# 08_Secure_Element.net
KiCad netlist of a schematic drawn in Altium Designer
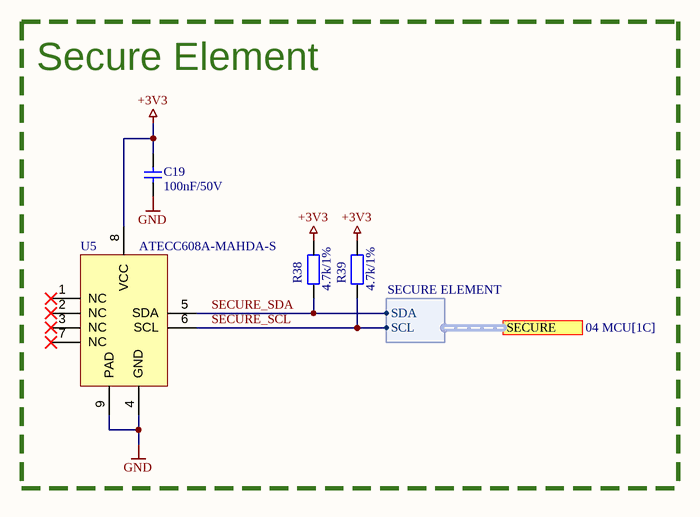
[diagram p0: 08 Secure Element.SchDoc]

(export (version "E")
  (design (tool "Eeschema 10.0.6"))
  (components
    (comp (ref "C19")
      (value "100nF/50V")
      (footprint "CAPC1005X06M-0402")
      (description "0.1 µF ±10% 50V Ceramic Capacitor X7R 0402 (1005 Metric)")
      (fields (field (name "MPN") "GRM155R71H104KE14D"))
      (libsource (lib "Symbol") (part "GRM155R71H104KE14D"))
    )
    (comp (ref "R38")
      (value "4.7k/1%")
      (footprint "RESC1005X04M-0402")
      (description "4.7 kOhms ±1% 0.063W, 1/16W Chip Resistor 0402 (1005 Metric) Moisture Resistant Thick Film")
      (fields (field (name "MPN") "RC0402FR-074K7L"))
      (libsource (lib "Symbol") (part "RC0402FR-074K7L"))
    )
    (comp (ref "R39")
      (value "4.7k/1%")
      (footprint "RESC1005X04M-0402")
      (description "4.7 kOhms ±1% 0.063W, 1/16W Chip Resistor 0402 (1005 Metric) Moisture Resistant Thick Film")
      (fields (field (name "MPN") "RC0402FR-074K7L"))
      (libsource (lib "Symbol") (part "RC0402FR-074K7L"))
    )
    (comp (ref "U5")
      (value "ATECC608A-MAHDA-S")
      (footprint "SON50P200X60_HS-9N")
      (description "Authentication Chip 8-UDFN (2x3)")
      (libsource (lib "Symbol") (part "ATECC608A-MAHDA-S"))
    )
  )
  (nets
    (net (code "3") (name "+3V3") (class "Default")
      (node (ref "C19") (pin "2") (pinfunction "2_2") (pintype "passive"))
      (node (ref "R38") (pin "2") (pinfunction "2_2") (pintype "passive"))
      (node (ref "R39") (pin "2") (pinfunction "2_2") (pintype "passive"))
      (node (ref "U5") (pin "8") (pinfunction "VCC_8") (pintype "passive"))
    )
    (net (code "4") (name "/SECURE_SCL") (class "Default")
      (node (ref "R39") (pin "1") (pinfunction "1_1") (pintype "passive"))
      (node (ref "U5") (pin "6") (pinfunction "SCL_6") (pintype "passive"))
    )
    (net (code "5") (name "/SECURE_SDA") (class "Default")
      (node (ref "R38") (pin "1") (pinfunction "1_1") (pintype "passive"))
      (node (ref "U5") (pin "5") (pinfunction "SDA_5") (pintype "passive"))
    )
    (net (code "7") (name "GND") (class "Default")
      (node (ref "C19") (pin "1") (pinfunction "1_1") (pintype "passive"))
      (node (ref "U5") (pin "4") (pinfunction "GND_4") (pintype "passive"))
      (node (ref "U5") (pin "9") (pinfunction "PAD_9") (pintype "passive"))
    )
    (net (code "8") (name "unconnected-(U5-NC-Pad1)") (class "Default")
      (node (ref "U5") (pin "1") (pinfunction "NC_1") (pintype "passive+no_connect"))
    )
    (net (code "9") (name "unconnected-(U5-NC-Pad2)") (class "Default")
      (node (ref "U5") (pin "2") (pinfunction "NC_2") (pintype "passive+no_connect"))
    )
    (net (code "10") (name "unconnected-(U5-NC-Pad3)") (class "Default")
      (node (ref "U5") (pin "3") (pinfunction "NC_3") (pintype "passive+no_connect"))
    )
    (net (code "11") (name "unconnected-(U5-NC-Pad7)") (class "Default")
      (node (ref "U5") (pin "7") (pinfunction "NC_7") (pintype "passive+no_connect"))
    )
  )
)
